# regulation.net
KiCad netlist of a schematic drawn in Altium Designer
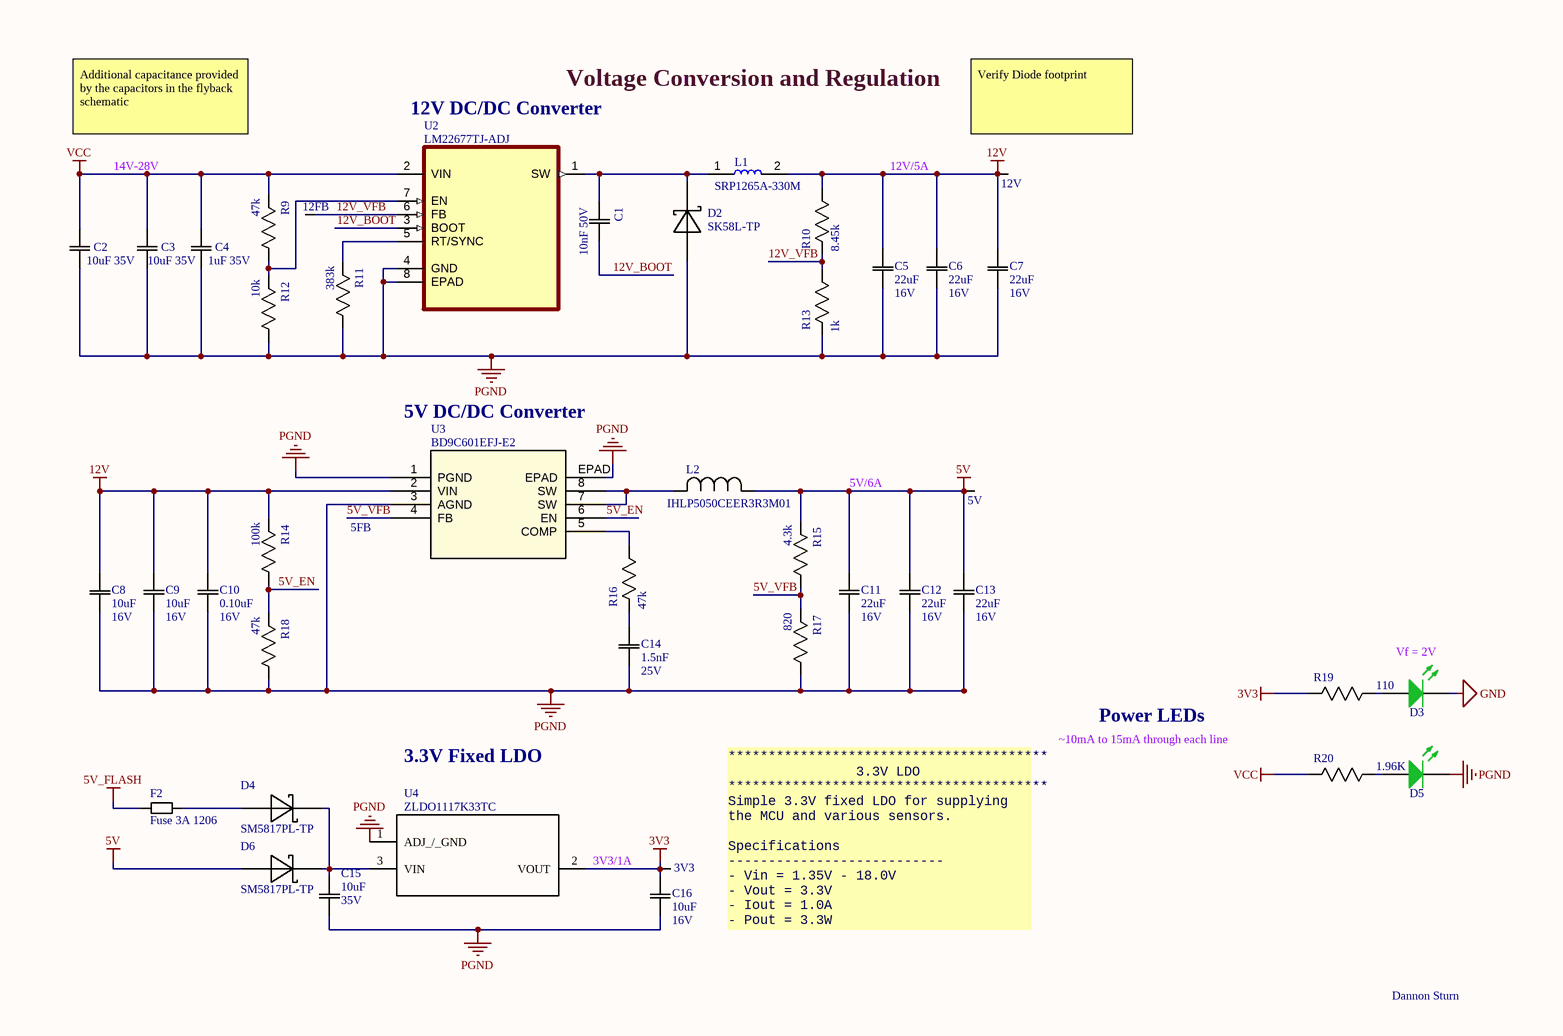
[diagram p0: regulation.SchDoc]

(export (version "E")
  (design (tool "Eeschema 10.0.6"))
  (components
    (comp (ref "3V3")
      (value "Test Point (Via)")
      (footprint "TP")
      (libsource (lib "AltiumLibraries") (part "Test Point (Via)"))
    )
    (comp (ref "5FB")
      (value "Test Point (Via)")
      (footprint "TP")
      (libsource (lib "AltiumLibraries") (part "Test Point (Via)"))
    )
    (comp (ref "5V")
      (value "Test Point (Via)")
      (footprint "TP")
      (libsource (lib "AltiumLibraries") (part "Test Point (Via)"))
    )
    (comp (ref "12FB")
      (value "Test Point (Via)")
      (footprint "TP")
      (libsource (lib "AltiumLibraries") (part "Test Point (Via)"))
    )
    (comp (ref "12V")
      (value "Test Point (Via)")
      (footprint "TP")
      (libsource (lib "AltiumLibraries") (part "Test Point (Via)"))
    )
    (comp (ref "C1")
      (value "10nF 50V")
      (footprint "0603")
      (description "CAP CER 10000PF 50V X7R 0805")
      (fields (field (name "TOLERANCE") "10%"))
      (libsource (lib "AltiumLibraries") (part "CAP 10nF 50V"))
    )
    (comp (ref "C2")
      (value "10uF 35V")
      (footprint "0805")
      (description "CAP CER 10uF 35V X5R 1206/0805")
      (fields (field (name "TOLERANCE") "10%"))
      (libsource (lib "AltiumLibraries") (part "CAP 10uF 35V"))
    )
    (comp (ref "C3")
      (value "10uF 35V")
      (footprint "0805")
      (description "CAP CER 10uF 35V X5R 1206/0805")
      (fields (field (name "TOLERANCE") "10%"))
      (libsource (lib "AltiumLibraries") (part "CAP 10uF 35V"))
    )
    (comp (ref "C4")
      (value "1uF 35V")
      (footprint "0805")
      (description "CAP CER 1UF 35V X7R 0805")
      (fields (field (name "TOLERANCE") "10%"))
      (libsource (lib "AltiumLibraries") (part "CAP 1uF 35V"))
    )
    (comp (ref "C5")
      (value "22uF")
      (footprint "0805")
      (description "CAP CER 22UF 16V X5R 0805")
      (fields (field (name "TOLERANCE") "10%") (field (name "RATING") "16V"))
      (libsource (lib "AltiumLibraries") (part "CAP 22uF 16V"))
    )
    (comp (ref "C6")
      (value "22uF")
      (footprint "0805")
      (description "CAP CER 22UF 16V X5R 0805")
      (fields (field (name "TOLERANCE") "10%") (field (name "RATING") "16V"))
      (libsource (lib "AltiumLibraries") (part "CAP 22uF 16V"))
    )
    (comp (ref "C7")
      (value "22uF")
      (footprint "0805")
      (description "CAP CER 22UF 16V X5R 0805")
      (fields (field (name "TOLERANCE") "10%") (field (name "RATING") "16V"))
      (libsource (lib "AltiumLibraries") (part "CAP 22uF 16V"))
    )
    (comp (ref "C8")
      (value "10uF")
      (footprint "0603")
      (description "CAP CER 10UF 16V X5R 0603/0805")
      (fields (field (name "TOLERANCE") "10%") (field (name "RATING") "16V"))
      (libsource (lib "AltiumLibraries") (part "CAP 10uF 16V"))
    )
    (comp (ref "C9")
      (value "10uF")
      (footprint "0603")
      (description "CAP CER 10UF 16V X5R 0603/0805")
      (fields (field (name "TOLERANCE") "10%") (field (name "RATING") "16V"))
      (libsource (lib "AltiumLibraries") (part "CAP 10uF 16V"))
    )
    (comp (ref "C10")
      (value "0.10uF")
      (footprint "0603")
      (description "CAP CER 0.10UF 16V X5R 0603/0805")
      (fields (field (name "TOLERANCE") "10%") (field (name "RATING") "16V"))
      (libsource (lib "AltiumLibraries") (part "CAP 0.10uF 16V"))
    )
    (comp (ref "C11")
      (value "22uF")
      (footprint "0805")
      (description "CAP CER 22UF 16V X5R 0805")
      (fields (field (name "TOLERANCE") "10%") (field (name "RATING") "16V"))
      (libsource (lib "AltiumLibraries") (part "CAP 22uF 16V"))
    )
    (comp (ref "C12")
      (value "22uF")
      (footprint "0805")
      (description "CAP CER 22UF 16V X5R 0805")
      (fields (field (name "TOLERANCE") "10%") (field (name "RATING") "16V"))
      (libsource (lib "AltiumLibraries") (part "CAP 22uF 16V"))
    )
    (comp (ref "C13")
      (value "22uF")
      (footprint "0805")
      (description "CAP CER 22UF 16V X5R 0805")
      (fields (field (name "TOLERANCE") "10%") (field (name "RATING") "16V"))
      (libsource (lib "AltiumLibraries") (part "CAP 22uF 16V"))
    )
    (comp (ref "C14")
      (value "1.5nF")
      (footprint "0603")
      (description "CAP CER 1500pF 25V X7R 0603")
      (fields (field (name "TOLERANCE") "1%") (field (name "RATING") "25V"))
      (libsource (lib "AltiumLibraries") (part "CAP 1500pF 25V"))
    )
    (comp (ref "C15")
      (value "10uF")
      (footprint "0805")
      (description "CAP CER 10uF 35V X5R 1206/0805")
      (fields
        (field (name "TOLERANCE") "10%")
        (field (name "RATING") "35V")
        (field (name "Comment") "10uF 35V")
      )
      (libsource (lib "AltiumLibraries") (part "CAP 10uF 35V"))
    )
    (comp (ref "C16")
      (value "10uF")
      (footprint "0603")
      (description "CAP CER 10UF 16V X5R 0603/0805")
      (fields (field (name "TOLERANCE") "10%") (field (name "RATING") "16V"))
      (libsource (lib "AltiumLibraries") (part "CAP 10uF 16V"))
    )
    (comp (ref "D2")
      (value "SK58L-TP")
      (footprint "DIOSC6959X240")
      (description "Diode Schottky 80V 5A Surface Mount SMA")
      (libsource (lib "AltiumLibraries") (part "DIODE SCHOTTKY 80V 5A"))
    )
    (comp (ref "D3")
      (value "LED2")
      (footprint "3.2X1.6X1.1")
      (description "Typical RED, GREEN, YELLOW, AMBER GaAs LED")
      (libsource (lib "AltiumLibraries") (part "LED GREEN SMD"))
    )
    (comp (ref "D4")
      (value "SM5817PL-TP")
      (footprint "SOD-123")
      (description "Diode Schottky 20V 1A Surface Mount SOD-123FL")
      (fields (field (name "MF") "Micro Commercial Co"))
      (libsource (lib "AltiumLibraries") (part "DIODE SCHOTTKY 20V 1A"))
    )
    (comp (ref "D5")
      (value "LED2")
      (footprint "3.2X1.6X1.1")
      (description "Typical RED, GREEN, YELLOW, AMBER GaAs LED")
      (libsource (lib "AltiumLibraries") (part "LED GREEN SMD"))
    )
    (comp (ref "D6")
      (value "SM5817PL-TP")
      (footprint "SOD-123")
      (description "Diode Schottky 20V 1A Surface Mount SOD-123FL")
      (fields (field (name "MF") "Micro Commercial Co"))
      (libsource (lib "AltiumLibraries") (part "DIODE SCHOTTKY 20V 1A"))
    )
    (comp (ref "F2")
      (value "Fuse 3A 1206")
      (footprint "1206")
      (description "FUSE 3A 63V AC/DC SLOW 1206")
      (libsource (lib "AltiumLibraries") (part "FUSE 3A 63V SLOW"))
    )
    (comp (ref "L1")
      (value "SRP1265A-330M")
      (footprint "IND_SRP1265A-330M")
      (description "33µH Shielded Wirewound Inductor 8A 58mOhm Max Nonstandard")
      (fields (field (name "MF") "Bourns"))
      (libsource (lib "AltiumLibraries") (part "IND 33UH 8A 58 MOHM SMD"))
    )
    (comp (ref "L2")
      (value "IHLP5050CEER3R3M01")
      (footprint "IND_IHLP-5050CE_VIS")
      (description "3.3uH 12A Shielded Molded Inductor 12mOhm Max")
      (fields (field (name "COPYRIGHT") "Copyright (C) 2021 Ultra Librarian. All rights reserved."))
      (libsource (lib "AltiumLibraries") (part "IND 3.3UH 12A 12 MOHM SMD"))
    )
    (comp (ref "R9")
      (value "47k")
      (footprint "0603")
      (description "RES SMD 47k OHM 5% 1/8W 0805")
      (fields (field (name "TOLERANCE") "5%"))
      (libsource (lib "AltiumLibraries") (part "RES 47k 1/8W - 5%"))
    )
    (comp (ref "R10")
      (value "8.45k")
      (footprint "0603")
      (description "RES SMD 8.45k OHM 1% 1/8W 0603")
      (fields (field (name "TOLERANCE") "1%"))
      (libsource (lib "AltiumLibraries") (part "RES 8.45k 1/8W"))
    )
    (comp (ref "R11")
      (value "383k")
      (footprint "0603")
      (description "RES SMD 383k OHM 1% 1/10W 0603")
      (fields (field (name "TOLERANCE") "1%"))
      (libsource (lib "AltiumLibraries") (part "RES 383k 1/10W"))
    )
    (comp (ref "R12")
      (value "10k")
      (footprint "0603")
      (description "RES SMD 10K OHM 5% 1/8W 0805/0603")
      (fields (field (name "TOLERANCE") "5%"))
      (libsource (lib "AltiumLibraries") (part "RES 10k 1/8W - 5%"))
    )
    (comp (ref "R13")
      (value "1k")
      (footprint "0603")
      (description "RES SMD 1K OHM 1% 1/8W 0603/0805")
      (fields (field (name "TOLERANCE") "1%"))
      (libsource (lib "AltiumLibraries") (part "RES 1k 1/8W - 1%"))
    )
    (comp (ref "R14")
      (value "100k")
      (footprint "0603")
      (description "RES SMD 100K OHM 5% 1/8W 0805/0603")
      (fields (field (name "TOLERANCE") "5%"))
      (libsource (lib "AltiumLibraries") (part "RES 100k 1/8W - 5%"))
    )
    (comp (ref "R15")
      (value "4.3k")
      (footprint "0603")
      (description "RES SMD 4.3K OHM 1% 1/10W 0603")
      (fields (field (name "TOLERANCE") "5%"))
      (libsource (lib "AltiumLibraries") (part "RES 4.3k 1/10W"))
    )
    (comp (ref "R16")
      (value "47k")
      (footprint "0603")
      (description "RES SMD 47K OHM 1% 1/8W 0805")
      (fields (field (name "TOLERANCE") "1%"))
      (libsource (lib "AltiumLibraries") (part "RES 47k 1/8W - 1%"))
    )
    (comp (ref "R17")
      (value "820")
      (footprint "0603")
      (description "RES SMD 820 OHM 1% 1/10W 0603")
      (fields (field (name "TOLERANCE") "1%"))
      (libsource (lib "AltiumLibraries") (part "RES 820 1/10W"))
    )
    (comp (ref "R18")
      (value "47k")
      (footprint "0603")
      (description "RES SMD 47k OHM 5% 1/8W 0805")
      (fields (field (name "TOLERANCE") "5%"))
      (libsource (lib "AltiumLibraries") (part "RES 47k 1/8W - 5%"))
    )
    (comp (ref "R19")
      (value "110")
      (footprint "0603")
      (description "RES SMD 110 OHM 1% 1/8W 0805/0603")
      (fields (field (name "TOLERANCE") "1%"))
      (libsource (lib "AltiumLibraries") (part "RES 110.0 1/8W - 1%"))
    )
    (comp (ref "R20")
      (value "1.96K")
      (footprint "0603")
      (description "RES SMD 1.96K OHM 1% 1/8W 0805")
      (fields (field (name "TOLERANCE") "1%"))
      (libsource (lib "AltiumLibraries") (part "RES 1.96k 1/8W"))
    )
    (comp (ref "U2")
      (value "LM22677TJ-ADJ")
      (footprint "TO127P1435X210-8N")
      (description "3A SIMPLE SWITCHERÂ®, Step-Down Voltage Regulator")
      (libsource (lib "AltiumLibraries") (part "LM22677TJ-ADJ"))
    )
    (comp (ref "U3")
      (value "BD9C601EFJ-E2")
      (footprint "HTSOP-J8_ROM-BD9C601EFJ-E2")
      (description "IC REG BUCK ADJ 6A 8HTSOP-J")
      (fields (field (name "COPYRIGHT") "Copyright (C) 2021 Ultra Librarian. All rights reserved."))
      (libsource (lib "AltiumLibraries") (part "BD9C601EFJ-E2"))
    )
    (comp (ref "U4")
      (value "ZLDO1117K33TC")
      (footprint "DPAK (TO-252)")
      (description "Linear Voltage Regulator IC Positive Fixed 1 Output  1A TO-252-3")
      (fields (field (name "MF") "Diodes Incorporated"))
      (libsource (lib "AltiumLibraries") (part "ZLDO1117K33TC"))
    )
  )
  (nets
    (net (code "1") (name "/5V_EN") (class "Default")
      (node (ref "R14") (pin "1") (pinfunction "R1_1") (pintype "passive"))
      (node (ref "R18") (pin "2") (pinfunction "R2_2") (pintype "passive"))
      (node (ref "U3") (pin "6") (pinfunction "EN_6") (pintype "passive"))
    )
    (net (code "2") (name "/5V_VFB") (class "Default")
      (node (ref "5FB") (pin "1") (pinfunction "1_1") (pintype "passive"))
      (node (ref "R15") (pin "1") (pinfunction "R1_1") (pintype "passive"))
      (node (ref "R17") (pin "2") (pinfunction "R2_2") (pintype "passive"))
      (node (ref "U3") (pin "4") (pinfunction "FB_4") (pintype "passive"))
    )
    (net (code "3") (name "/12V_BOOT") (class "Default")
      (node (ref "C1") (pin "2") (pinfunction "C2_2") (pintype "passive"))
      (node (ref "U2") (pin "3") (pinfunction "BOOT_3") (pintype "input"))
    )
    (net (code "4") (name "/12V_VFB") (class "Default")
      (node (ref "12FB") (pin "1") (pinfunction "1_1") (pintype "passive"))
      (node (ref "R10") (pin "2") (pinfunction "R2_2") (pintype "passive"))
      (node (ref "R13") (pin "1") (pinfunction "R1_1") (pintype "passive"))
      (node (ref "U2") (pin "6") (pinfunction "FB_6") (pintype "input"))
    )
    (net (code "5") (name "3V3") (class "Default")
      (node (ref "3V3") (pin "1") (pinfunction "1_1") (pintype "passive"))
      (node (ref "C16") (pin "2") (pinfunction "C2_2") (pintype "passive"))
      (node (ref "R19") (pin "2") (pinfunction "R2_2") (pintype "passive"))
      (node (ref "U4") (pin "2") (pinfunction "VOUT_2") (pintype "power_in"))
    )
    (net (code "6") (name "5V") (class "Default")
      (node (ref "5V") (pin "1") (pinfunction "1_1") (pintype "passive"))
      (node (ref "C11") (pin "1") (pinfunction "C1_1") (pintype "passive"))
      (node (ref "C12") (pin "1") (pinfunction "C1_1") (pintype "passive"))
      (node (ref "C13") (pin "1") (pinfunction "C1_1") (pintype "passive"))
      (node (ref "D6") (pin "A") (pinfunction "A_A") (pintype "passive"))
      (node (ref "L2") (pin "1") (pinfunction "1_1") (pintype "passive"))
      (node (ref "R15") (pin "2") (pinfunction "R2_2") (pintype "passive"))
    )
    (net (code "7") (name "5V_FLASH") (class "Default")
      (node (ref "F2") (pin "1") (pinfunction "1_1") (pintype "passive"))
    )
    (net (code "8") (name "12V") (class "Default")
      (node (ref "12V") (pin "1") (pinfunction "1_1") (pintype "passive"))
      (node (ref "C10") (pin "1") (pinfunction "C1_1") (pintype "passive"))
      (node (ref "C5") (pin "2") (pinfunction "C2_2") (pintype "passive"))
      (node (ref "C6") (pin "2") (pinfunction "C2_2") (pintype "passive"))
      (node (ref "C7") (pin "2") (pinfunction "C2_2") (pintype "passive"))
      (node (ref "C8") (pin "2") (pinfunction "C2_2") (pintype "passive"))
      (node (ref "C9") (pin "1") (pinfunction "C1_1") (pintype "passive"))
      (node (ref "L1") (pin "2") (pinfunction "2_2") (pintype "passive"))
      (node (ref "R10") (pin "1") (pinfunction "R1_1") (pintype "passive"))
      (node (ref "R14") (pin "2") (pinfunction "R2_2") (pintype "passive"))
      (node (ref "U3") (pin "2") (pinfunction "VIN_2") (pintype "passive"))
    )
    (net (code "9") (name "GND") (class "Default")
      (node (ref "D3") (pin "2") (pinfunction "K_2") (pintype "passive"))
    )
    (net (code "10") (name "Net-(C1-C1)") (class "Default")
      (node (ref "C1") (pin "1") (pinfunction "C1_1") (pintype "passive"))
      (node (ref "D2") (pin "C") (pinfunction "K_C") (pintype "passive"))
      (node (ref "L1") (pin "1") (pinfunction "1_1") (pintype "passive"))
      (node (ref "U2") (pin "1") (pinfunction "SW_1") (pintype "output"))
    )
    (net (code "11") (name "Net-(C14-C2)") (class "Default")
      (node (ref "C14") (pin "2") (pinfunction "C2_2") (pintype "passive"))
      (node (ref "R16") (pin "2") (pinfunction "R2_2") (pintype "passive"))
    )
    (net (code "12") (name "Net-(C15-C1)") (class "Default")
      (node (ref "C15") (pin "1") (pinfunction "C1_1") (pintype "passive"))
      (node (ref "D4") (pin "C") (pinfunction "K_C") (pintype "passive"))
      (node (ref "D6") (pin "C") (pinfunction "K_C") (pintype "passive"))
      (node (ref "U4") (pin "3") (pinfunction "VIN_3") (pintype "power_in"))
    )
    (net (code "13") (name "Net-(D3-A)") (class "Default")
      (node (ref "D3") (pin "1") (pinfunction "A_1") (pintype "passive"))
      (node (ref "R19") (pin "1") (pinfunction "R1_1") (pintype "passive"))
    )
    (net (code "14") (name "Net-(D4-PadA)") (class "Default")
      (node (ref "D4") (pin "A") (pinfunction "A_A") (pintype "passive"))
      (node (ref "F2") (pin "2") (pinfunction "2_2") (pintype "passive"))
    )
    (net (code "15") (name "Net-(D5-A)") (class "Default")
      (node (ref "D5") (pin "1") (pinfunction "A_1") (pintype "passive"))
      (node (ref "R20") (pin "1") (pinfunction "R1_1") (pintype "passive"))
    )
    (net (code "16") (name "Net-(L2-Pad2)") (class "Default")
      (node (ref "L2") (pin "2") (pinfunction "2_2") (pintype "passive"))
      (node (ref "U3") (pin "7") (pinfunction "SW_7") (pintype "passive"))
      (node (ref "U3") (pin "8") (pinfunction "SW_8") (pintype "passive"))
    )
    (net (code "17") (name "Net-(R11-R2)") (class "Default")
      (node (ref "R11") (pin "2") (pinfunction "R2_2") (pintype "passive"))
      (node (ref "U2") (pin "5") (pinfunction "RT/SYNC_5") (pintype "passive"))
    )
    (net (code "18") (name "Net-(R12-R2)") (class "Default")
      (node (ref "R12") (pin "2") (pinfunction "R2_2") (pintype "passive"))
      (node (ref "R9") (pin "1") (pinfunction "R1_1") (pintype "passive"))
      (node (ref "U2") (pin "7") (pinfunction "EN_7") (pintype "input"))
    )
    (net (code "19") (name "Net-(R16-R1)") (class "Default")
      (node (ref "R16") (pin "1") (pinfunction "R1_1") (pintype "passive"))
      (node (ref "U3") (pin "5") (pinfunction "COMP_5") (pintype "passive"))
    )
    (net (code "20") (name "PGND") (class "Default")
      (node (ref "C10") (pin "2") (pinfunction "C2_2") (pintype "passive"))
      (node (ref "C11") (pin "2") (pinfunction "C2_2") (pintype "passive"))
      (node (ref "C12") (pin "2") (pinfunction "C2_2") (pintype "passive"))
      (node (ref "C13") (pin "2") (pinfunction "C2_2") (pintype "passive"))
      (node (ref "C14") (pin "1") (pinfunction "C1_1") (pintype "passive"))
      (node (ref "C15") (pin "2") (pinfunction "C2_2") (pintype "passive"))
      (node (ref "C16") (pin "1") (pinfunction "C1_1") (pintype "passive"))
      (node (ref "C2") (pin "2") (pinfunction "C2_2") (pintype "passive"))
      (node (ref "C3") (pin "2") (pinfunction "C2_2") (pintype "passive"))
      (node (ref "C4") (pin "2") (pinfunction "C2_2") (pintype "passive"))
      (node (ref "C5") (pin "1") (pinfunction "C1_1") (pintype "passive"))
      (node (ref "C6") (pin "1") (pinfunction "C1_1") (pintype "passive"))
      (node (ref "C7") (pin "1") (pinfunction "C1_1") (pintype "passive"))
      (node (ref "C8") (pin "1") (pinfunction "C1_1") (pintype "passive"))
      (node (ref "C9") (pin "2") (pinfunction "C2_2") (pintype "passive"))
      (node (ref "D2") (pin "A") (pinfunction "A_A") (pintype "passive"))
      (node (ref "D5") (pin "2") (pinfunction "K_2") (pintype "passive"))
      (node (ref "R11") (pin "1") (pinfunction "R1_1") (pintype "passive"))
      (node (ref "R12") (pin "1") (pinfunction "R1_1") (pintype "passive"))
      (node (ref "R13") (pin "2") (pinfunction "R2_2") (pintype "passive"))
      (node (ref "R17") (pin "1") (pinfunction "R1_1") (pintype "passive"))
      (node (ref "R18") (pin "1") (pinfunction "R1_1") (pintype "passive"))
      (node (ref "U2") (pin "4") (pinfunction "GND_4") (pintype "passive"))
      (node (ref "U2") (pin "8") (pinfunction "EPAD_8") (pintype "passive"))
      (node (ref "U3") (pin "1") (pinfunction "PGND_1") (pintype "passive"))
      (node (ref "U3") (pin "3") (pinfunction "AGND_3") (pintype "passive"))
      (node (ref "U3") (pin "EPAD") (pinfunction "EPAD_EPAD") (pintype "passive"))
      (node (ref "U4") (pin "1") (pinfunction "ADJ_/_GND_1") (pintype "power_in"))
    )
    (net (code "21") (name "VCC") (class "Default")
      (node (ref "C2") (pin "1") (pinfunction "C1_1") (pintype "passive"))
      (node (ref "C3") (pin "1") (pinfunction "C1_1") (pintype "passive"))
      (node (ref "C4") (pin "1") (pinfunction "C1_1") (pintype "passive"))
      (node (ref "R20") (pin "2") (pinfunction "R2_2") (pintype "passive"))
      (node (ref "R9") (pin "2") (pinfunction "R2_2") (pintype "passive"))
      (node (ref "U2") (pin "2") (pinfunction "VIN_2") (pintype "power_in"))
    )
  )
)
